# untitled.net
KiCad netlist of a schematic drawn in EAGLE
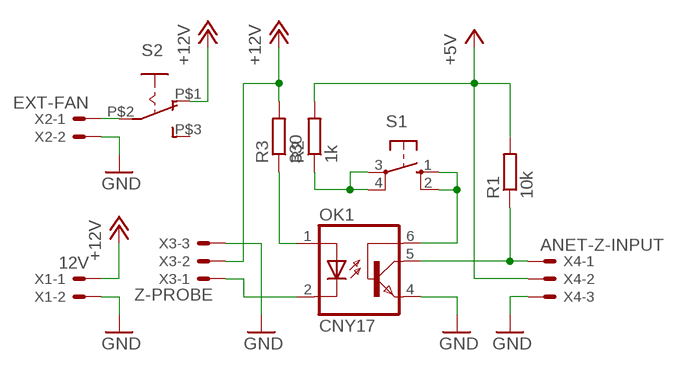
[diagram p0: schematic, sheet 1]

(export (version "E")
  (design (tool "Eeschema 10.0.6"))
  (components
    (comp (ref "OK1")
      (value "CNY17")
      (footprint "eagle-import:DIL06")
      (fields (field (name "MPN") "CNY17-1"))
      (libsource (lib "eagle-import") (part "CNY17"))
    )
    (comp (ref "R1")
      (value "10k")
      (footprint "eagle-import:M0805")
      (libsource (lib "eagle-import") (part "R-EU_M0805"))
    )
    (comp (ref "R2")
      (value "1k")
      (footprint "eagle-import:M0805")
      (libsource (lib "eagle-import") (part "R-EU_M0805"))
    )
    (comp (ref "R3")
      (value "330")
      (footprint "eagle-import:M0805")
      (libsource (lib "eagle-import") (part "R-EU_M0805"))
    )
    (comp (ref "S1")
      (value "10-XX")
      (footprint "eagle-import:B3F-10XX")
      (fields (field (name "MPN") "B3F-1000"))
      (libsource (lib "eagle-import") (part "10-XX"))
    )
    (comp (ref "S2")
      (value "EG1218THIN")
      (footprint "eagle-import:THIN")
      (libsource (lib "eagle-import") (part "EG1218THIN"))
    )
    (comp (ref "X1")
      (value "12V")
      (footprint "eagle-import:JST-XH-02-PACKAGE-LONG-PAD")
      (libsource (lib "eagle-import") (part "JST-XH-02-PIN-LONG-PAD"))
    )
    (comp (ref "X2")
      (value "EXT-FAN")
      (footprint "eagle-import:JST-XH-02-PACKAGE-LONG-PAD")
      (libsource (lib "eagle-import") (part "JST-XH-02-PIN-LONG-PAD"))
    )
    (comp (ref "X3")
      (value "Z-PROBE")
      (footprint "eagle-import:JST-XH-03-PACKAGE-LONG-PAD")
      (libsource (lib "eagle-import") (part "JST-XH-03-PIN-LONG-PAD"))
    )
    (comp (ref "X4")
      (value "ANET-Z-INPUT")
      (footprint "eagle-import:JST-XH-03-PACKAGE-LONG-PAD")
      (libsource (lib "eagle-import") (part "JST-XH-03-PIN-LONG-PAD"))
    )
  )
  (nets
    (net (code "1") (name "+5V") (class "Default")
      (node (ref "R1") (pin "2") (pinfunction "2_2") (pintype "passive"))
      (node (ref "R2") (pin "2") (pinfunction "2_2") (pintype "passive"))
      (node (ref "X4") (pin "2") (pinfunction "S_2") (pintype "passive"))
    )
    (net (code "2") (name "+12V") (class "Default")
      (node (ref "R3") (pin "2") (pinfunction "2_2") (pintype "passive"))
      (node (ref "S2") (pin "P$1") (pinfunction "O_P$1") (pintype "passive"))
      (node (ref "X1") (pin "1") (pinfunction "S_1") (pintype "passive"))
      (node (ref "X3") (pin "2") (pinfunction "S_2") (pintype "passive"))
    )
    (net (code "3") (name "GND") (class "Default")
      (node (ref "OK1") (pin "4") (pinfunction "EMI_4") (pintype "passive"))
      (node (ref "X1") (pin "2") (pinfunction "S_2") (pintype "passive"))
      (node (ref "X2") (pin "2") (pinfunction "S_2") (pintype "passive"))
      (node (ref "X3") (pin "3") (pinfunction "S_3") (pintype "passive"))
      (node (ref "X4") (pin "3") (pinfunction "S_3") (pintype "passive"))
    )
    (net (code "4") (name "Net-(OK1-A)") (class "Default")
      (node (ref "OK1") (pin "1") (pinfunction "A_1") (pintype "passive"))
      (node (ref "R3") (pin "1") (pinfunction "1_1") (pintype "passive"))
    )
    (net (code "5") (name "Net-(OK1-BAS)") (class "Default")
      (node (ref "OK1") (pin "6") (pinfunction "BAS_6") (pintype "passive"))
      (node (ref "S1") (pin "1") (pinfunction "S_1") (pintype "passive"))
      (node (ref "S1") (pin "2") (pinfunction "S1_2") (pintype "passive"))
    )
    (net (code "6") (name "Net-(OK1-C)") (class "Default")
      (node (ref "OK1") (pin "2") (pinfunction "C_2") (pintype "passive"))
      (node (ref "X3") (pin "1") (pinfunction "S_1") (pintype "passive"))
    )
    (net (code "7") (name "Net-(OK1-COL)") (class "Default")
      (node (ref "OK1") (pin "5") (pinfunction "COL_5") (pintype "passive"))
      (node (ref "R1") (pin "1") (pinfunction "1_1") (pintype "passive"))
      (node (ref "X4") (pin "1") (pinfunction "S_1") (pintype "passive"))
    )
    (net (code "8") (name "Net-(S1-P)") (class "Default")
      (node (ref "R2") (pin "1") (pinfunction "1_1") (pintype "passive"))
      (node (ref "S1") (pin "3") (pinfunction "P_3") (pintype "passive"))
      (node (ref "S1") (pin "4") (pinfunction "P1_4") (pintype "passive"))
    )
    (net (code "9") (name "Net-(S2-P)") (class "Default")
      (node (ref "S2") (pin "P$2") (pinfunction "P_P$2") (pintype "passive"))
      (node (ref "X2") (pin "1") (pinfunction "S_1") (pintype "passive"))
    )
    (net (code "10") (name "unconnected-(S2-S-PadP$3)") (class "Default")
      (node (ref "S2") (pin "P$3") (pinfunction "S_P$3") (pintype "passive"))
    )
  )
)
